# blood-pressure-input-reference-custom-te.net
KiCad netlist of a schematic drawn in Altium Designer
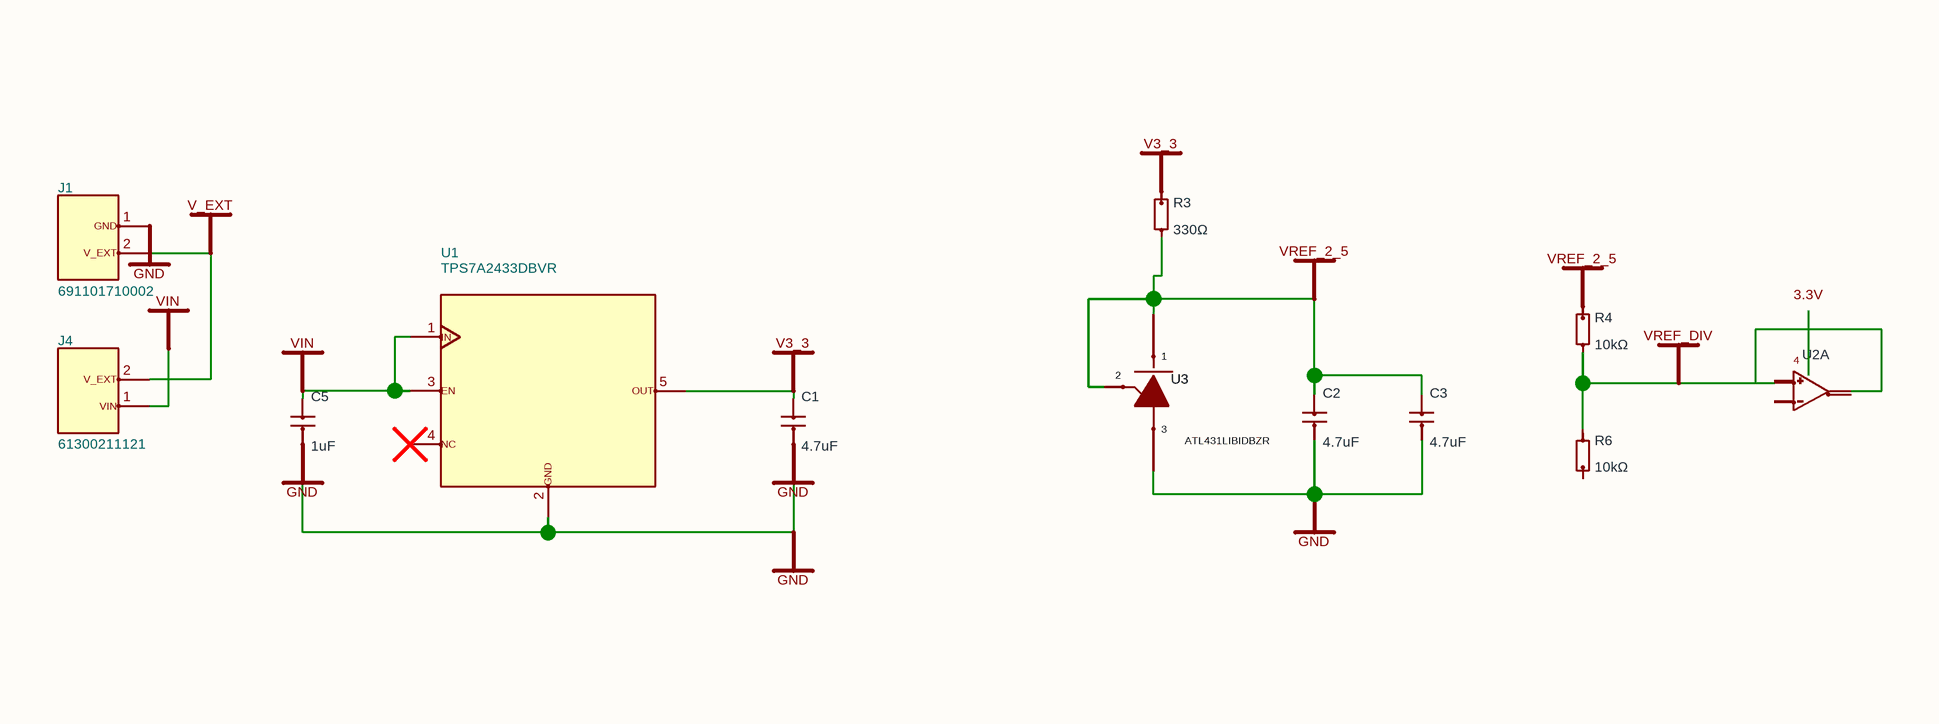
[diagram p0: blood-pressure-input-reference-custom-text.SchDoc]

(export (version "E")
  (design (tool "Eeschema 10.0.6"))
  (components
    (comp (ref "C1") (value "4.7uF") (libsource (lib "altium-import") (part "root_0_capacitor_down_")))
    (comp (ref "C2") (value "4.7uF") (libsource (lib "altium-import") (part "root_0_capacitor_down_")))
    (comp (ref "C3") (value "4.7uF") (libsource (lib "altium-import") (part "root_0_capacitor_down_")))
    (comp (ref "C5") (value "1uF") (libsource (lib "altium-import") (part "root_0_capacitor_down_")))
    (comp (ref "J1") (value "~") (libsource (lib "altium-import") (part "root_0_J1_")))
    (comp (ref "J4") (value "~") (libsource (lib "altium-import") (part "root_0_J4_")))
    (comp (ref "R3") (value "330Ω") (libsource (lib "altium-import") (part "root_0_boxresistor_down_")))
    (comp (ref "R4") (value "10kΩ") (libsource (lib "altium-import") (part "root_0_boxresistor_down_")))
    (comp (ref "R6") (value "10kΩ") (libsource (lib "") (part "root_0_boxresistor_down__1")))
    (comp (ref "U1") (value "~") (libsource (lib "altium-import") (part "root_0_U1_")))
    (comp (ref "U2A") (value "~") (libsource (lib "altium-import") (part "root_0_opamp_no_power_right_")))
    (comp (ref "U3") (value "~") (libsource (lib "altium-import") (part "root_0_U3_")))
  )
  (nets
    (net (code "1") (name "GND") (class "Default")
      (node (ref "C1") (pin "2") (pinfunction "cathode_2") (pintype "passive"))
      (node (ref "C2") (pin "2") (pinfunction "cathode_2") (pintype "passive"))
      (node (ref "C3") (pin "2") (pinfunction "cathode_2") (pintype "passive"))
      (node (ref "C5") (pin "2") (pinfunction "cathode_2") (pintype "passive"))
      (node (ref "J1") (pin "1") (pinfunction "GND_1") (pintype "passive"))
      (node (ref "U1") (pin "2") (pinfunction "GND_2") (pintype "passive"))
      (node (ref "U3") (pin "3") (pinfunction "A_3") (pintype "passive"))
    )
    (net (code "2") (name "V3_3") (class "Default")
      (node (ref "C1") (pin "1") (pinfunction "anode_1") (pintype "passive"))
      (node (ref "R3") (pin "1") (pinfunction "anode_1") (pintype "passive"))
      (node (ref "U1") (pin "5") (pinfunction "OUT_5") (pintype "output"))
    )
    (net (code "3") (name "VIN") (class "Default")
      (node (ref "C5") (pin "1") (pinfunction "anode_1") (pintype "passive"))
      (node (ref "J4") (pin "1") (pinfunction "VIN_1") (pintype "passive"))
      (node (ref "U1") (pin "1") (pinfunction "IN_1") (pintype "input"))
      (node (ref "U1") (pin "3") (pinfunction "EN_3") (pintype "passive"))
    )
    (net (code "4") (name "VREF_2_5") (class "Default")
      (node (ref "C2") (pin "1") (pinfunction "anode_1") (pintype "passive"))
      (node (ref "C3") (pin "1") (pinfunction "anode_1") (pintype "passive"))
      (node (ref "R3") (pin "2") (pinfunction "cathode_2") (pintype "passive"))
      (node (ref "R4") (pin "1") (pinfunction "anode_1") (pintype "passive"))
      (node (ref "U3") (pin "1") (pinfunction "K_1") (pintype "passive"))
      (node (ref "U3") (pin "2") (pinfunction "R_2") (pintype "passive"))
    )
    (net (code "5") (name "VREF_DIV") (class "Default")
      (node (ref "R4") (pin "2") (pinfunction "cathode_2") (pintype "passive"))
      (node (ref "R6") (pin "1") (pinfunction "anode_1") (pintype "passive"))
      (node (ref "U2A") (pin "3") (pinfunction "inp1_3") (pintype "passive"))
    )
    (net (code "7") (name "V_EXT") (class "Default")
      (node (ref "J1") (pin "2") (pinfunction "V_EXT_2") (pintype "passive"))
      (node (ref "J4") (pin "2") (pinfunction "V_EXT_2") (pintype "passive"))
    )
    (net (code "8") (name "unconnected-(R6-cathode-Pad2)") (class "Default")
      (node (ref "R6") (pin "2") (pinfunction "cathode_2") (pintype "passive"))
    )
    (net (code "9") (name "unconnected-(U1-NC-Pad4)") (class "Default")
      (node (ref "U1") (pin "4") (pinfunction "NC_4") (pintype "passive+no_connect"))
    )
    (net (code "10") (name "unconnected-(U2A-inp2-Pad2)") (class "Default")
      (node (ref "U2A") (pin "2") (pinfunction "inp2_2") (pintype "passive"))
    )
    (net (code "11") (name "unconnected-(U2A-out-Pad1)") (class "Default")
      (node (ref "U2A") (pin "1") (pinfunction "out_1") (pintype "passive"))
    )
  )
)
